# protel_wireless_remote.net
KiCad netlist of a schematic drawn in Altium Designer
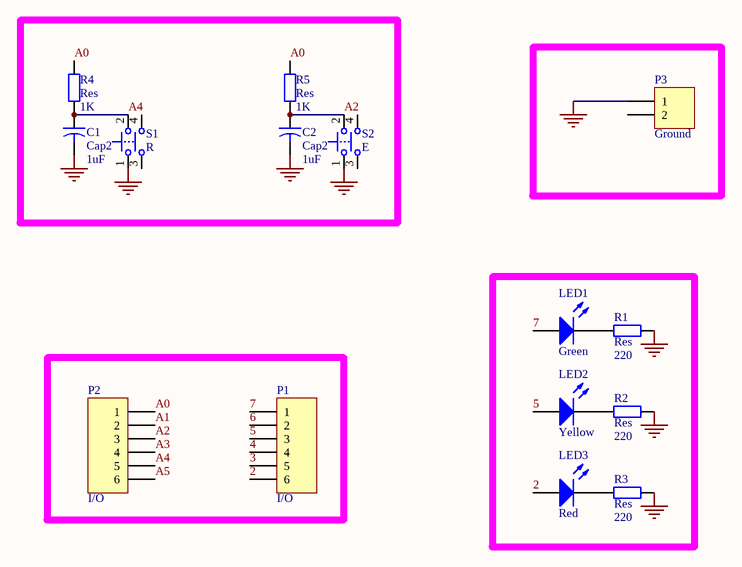
[diagram p0: protel_wireless_remote.SchDoc]

(export (version "E")
  (design (tool "Eeschema 10.0.6"))
  (components
    (comp (ref "C1")
      (value "Cap2")
      (footprint "CAPR5-4X5")
      (description "Capacitor")
      (fields (field (name "ALTIUM_VALUE") "1uF") (field (name "PUBLISHER") "Altium Limited"))
      (libsource (lib "Miscellaneous Devices") (part "Cap2"))
    )
    (comp (ref "C2")
      (value "Cap2")
      (footprint "CAPR5-4X5")
      (description "Capacitor")
      (fields (field (name "ALTIUM_VALUE") "1uF") (field (name "PUBLISHER") "Altium Limited"))
      (libsource (lib "Miscellaneous Devices") (part "Cap2"))
    )
    (comp (ref "LED1")
      (value "Green")
      (footprint "LED-1")
      (description "Typical RED GaAs LED")
      (fields (field (name "PUBLISHER") "Altium Limited"))
      (libsource (lib "Miscellaneous Devices") (part "LED1"))
    )
    (comp (ref "LED2")
      (value "Yellow")
      (footprint "LED-1")
      (description "Typical RED GaAs LED")
      (fields (field (name "PUBLISHER") "Altium Limited"))
      (libsource (lib "Miscellaneous Devices") (part "LED1"))
    )
    (comp (ref "LED3")
      (value "Red")
      (footprint "LED-1")
      (description "Typical RED GaAs LED")
      (fields (field (name "PUBLISHER") "Altium Limited"))
      (libsource (lib "Miscellaneous Devices") (part "LED1"))
    )
    (comp (ref "P1")
      (value "I/O")
      (footprint "HDR1X6")
      (description "Header, 6-Pin")
      (fields (field (name "PUBLISHER") "Altium Limited"))
      (libsource (lib "Miscellaneous Connectors") (part "Header 6"))
    )
    (comp (ref "P2")
      (value "I/O")
      (footprint "HDR1X6")
      (description "Header, 6-Pin")
      (fields (field (name "PUBLISHER") "Altium Limited"))
      (libsource (lib "") (part "Header 6_1"))
    )
    (comp (ref "P3")
      (value "Ground")
      (footprint "HDR1X2")
      (description "Header, 2-Pin")
      (fields (field (name "PUBLISHER") "Altium Limited"))
      (libsource (lib "Miscellaneous Connectors") (part "Header 2"))
    )
    (comp (ref "R1")
      (value "Res")
      (footprint "AXIAL-0.4")
      (description "Resistor")
      (fields (field (name "ALTIUM_VALUE") "220") (field (name "PUBLISHER") "Altium Limited"))
      (libsource (lib "Miscellaneous Devices") (part "Res2"))
    )
    (comp (ref "R2")
      (value "Res")
      (footprint "AXIAL-0.4")
      (description "Resistor")
      (fields (field (name "ALTIUM_VALUE") "220") (field (name "PUBLISHER") "Altium Limited"))
      (libsource (lib "Miscellaneous Devices") (part "Res2"))
    )
    (comp (ref "R3")
      (value "Res")
      (footprint "AXIAL-0.4")
      (description "Resistor")
      (fields (field (name "ALTIUM_VALUE") "220") (field (name "PUBLISHER") "Altium Limited"))
      (libsource (lib "Miscellaneous Devices") (part "Res2"))
    )
    (comp (ref "R4")
      (value "Res")
      (footprint "AXIAL-0.4")
      (description "Resistor")
      (fields (field (name "ALTIUM_VALUE") "1K") (field (name "PUBLISHER") "Altium Limited"))
      (libsource (lib "") (part "Res2_1"))
    )
    (comp (ref "R5")
      (value "Res")
      (footprint "AXIAL-0.4")
      (description "Resistor")
      (fields (field (name "ALTIUM_VALUE") "1K") (field (name "PUBLISHER") "Altium Limited"))
      (libsource (lib "") (part "Res2_1"))
    )
    (comp (ref "S1")
      (value "R")
      (footprint "IT-2175")
      (description "Tactile Switch, DPST; Thru-Hole; Vertical; Rating DC 12V, 50mA (max)")
      (fields (field (name "PUBLISHER") "Altium Limited"))
      (libsource (lib "IL Switch Push Button") (part "IT-2175"))
    )
    (comp (ref "S2")
      (value "E")
      (footprint "IT-2175")
      (description "Tactile Switch, DPST; Thru-Hole; Vertical; Rating DC 12V, 50mA (max)")
      (fields (field (name "PUBLISHER") "Altium Limited"))
      (libsource (lib "IL Switch Push Button") (part "IT-2175"))
    )
  )
  (nets
    (net (code "1") (name "/2") (class "Default")
      (node (ref "LED3") (pin "1") (pinfunction "A_1") (pintype "passive"))
      (node (ref "P1") (pin "6") (pinfunction "6_6") (pintype "passive"))
    )
    (net (code "2") (name "/3") (class "Default")
      (node (ref "P1") (pin "5") (pinfunction "5_5") (pintype "passive"))
    )
    (net (code "3") (name "/4") (class "Default")
      (node (ref "P1") (pin "4") (pinfunction "4_4") (pintype "passive"))
    )
    (net (code "4") (name "/5") (class "Default")
      (node (ref "LED2") (pin "1") (pinfunction "A_1") (pintype "passive"))
      (node (ref "P1") (pin "3") (pinfunction "3_3") (pintype "passive"))
    )
    (net (code "5") (name "/6") (class "Default")
      (node (ref "P1") (pin "2") (pinfunction "2_2") (pintype "passive"))
    )
    (net (code "6") (name "/7") (class "Default")
      (node (ref "LED1") (pin "1") (pinfunction "A_1") (pintype "passive"))
      (node (ref "P1") (pin "1") (pinfunction "1_1") (pintype "passive"))
    )
    (net (code "7") (name "/A0") (class "Default")
      (node (ref "P2") (pin "1") (pinfunction "1_1") (pintype "passive"))
      (node (ref "R4") (pin "2") (pinfunction "2_2") (pintype "passive"))
      (node (ref "R5") (pin "2") (pinfunction "2_2") (pintype "passive"))
    )
    (net (code "8") (name "/A1") (class "Default")
      (node (ref "P2") (pin "2") (pinfunction "2_2") (pintype "passive"))
    )
    (net (code "9") (name "/A2") (class "Default")
      (node (ref "C2") (pin "1") (pinfunction "1_1") (pintype "passive"))
      (node (ref "P2") (pin "3") (pinfunction "3_3") (pintype "passive"))
      (node (ref "R5") (pin "1") (pinfunction "1_1") (pintype "passive"))
      (node (ref "S2") (pin "2") (pinfunction "2_2") (pintype "passive"))
    )
    (net (code "10") (name "/A3") (class "Default")
      (node (ref "P2") (pin "4") (pinfunction "4_4") (pintype "passive"))
    )
    (net (code "11") (name "/A4") (class "Default")
      (node (ref "C1") (pin "1") (pinfunction "1_1") (pintype "passive"))
      (node (ref "P2") (pin "5") (pinfunction "5_5") (pintype "passive"))
      (node (ref "R4") (pin "1") (pinfunction "1_1") (pintype "passive"))
      (node (ref "S1") (pin "2") (pinfunction "2_2") (pintype "passive"))
    )
    (net (code "12") (name "/A5") (class "Default")
      (node (ref "P2") (pin "6") (pinfunction "6_6") (pintype "passive"))
    )
    (net (code "13") (name "GND") (class "Default")
      (node (ref "C1") (pin "2") (pinfunction "2_2") (pintype "passive"))
      (node (ref "C2") (pin "2") (pinfunction "2_2") (pintype "passive"))
      (node (ref "P3") (pin "1") (pinfunction "1_1") (pintype "passive"))
      (node (ref "R1") (pin "2") (pinfunction "2_2") (pintype "passive"))
      (node (ref "R2") (pin "2") (pinfunction "2_2") (pintype "passive"))
      (node (ref "R3") (pin "2") (pinfunction "2_2") (pintype "passive"))
      (node (ref "S1") (pin "1") (pinfunction "1_1") (pintype "passive"))
      (node (ref "S2") (pin "1") (pinfunction "1_1") (pintype "passive"))
    )
    (net (code "14") (name "Net-(LED1-K)") (class "Default")
      (node (ref "LED1") (pin "2") (pinfunction "K_2") (pintype "passive"))
      (node (ref "R1") (pin "1") (pinfunction "1_1") (pintype "passive"))
    )
    (net (code "15") (name "Net-(LED2-K)") (class "Default")
      (node (ref "LED2") (pin "2") (pinfunction "K_2") (pintype "passive"))
      (node (ref "R2") (pin "1") (pinfunction "1_1") (pintype "passive"))
    )
    (net (code "16") (name "Net-(LED3-K)") (class "Default")
      (node (ref "LED3") (pin "2") (pinfunction "K_2") (pintype "passive"))
      (node (ref "R3") (pin "1") (pinfunction "1_1") (pintype "passive"))
    )
    (net (code "17") (name "unconnected-(P3-Pad2)") (class "Default")
      (node (ref "P3") (pin "2") (pinfunction "2_2") (pintype "passive"))
    )
    (net (code "18") (name "unconnected-(S1-Pad3)") (class "Default")
      (node (ref "S1") (pin "3") (pinfunction "3_3") (pintype "passive"))
    )
    (net (code "19") (name "unconnected-(S1-Pad4)") (class "Default")
      (node (ref "S1") (pin "4") (pinfunction "4_4") (pintype "passive"))
    )
    (net (code "20") (name "unconnected-(S2-Pad3)") (class "Default")
      (node (ref "S2") (pin "3") (pinfunction "3_3") (pintype "passive"))
    )
    (net (code "21") (name "unconnected-(S2-Pad4)") (class "Default")
      (node (ref "S2") (pin "4") (pinfunction "4_4") (pintype "passive"))
    )
  )
)
